# untitled.net
KiCad netlist of a schematic drawn in EAGLE
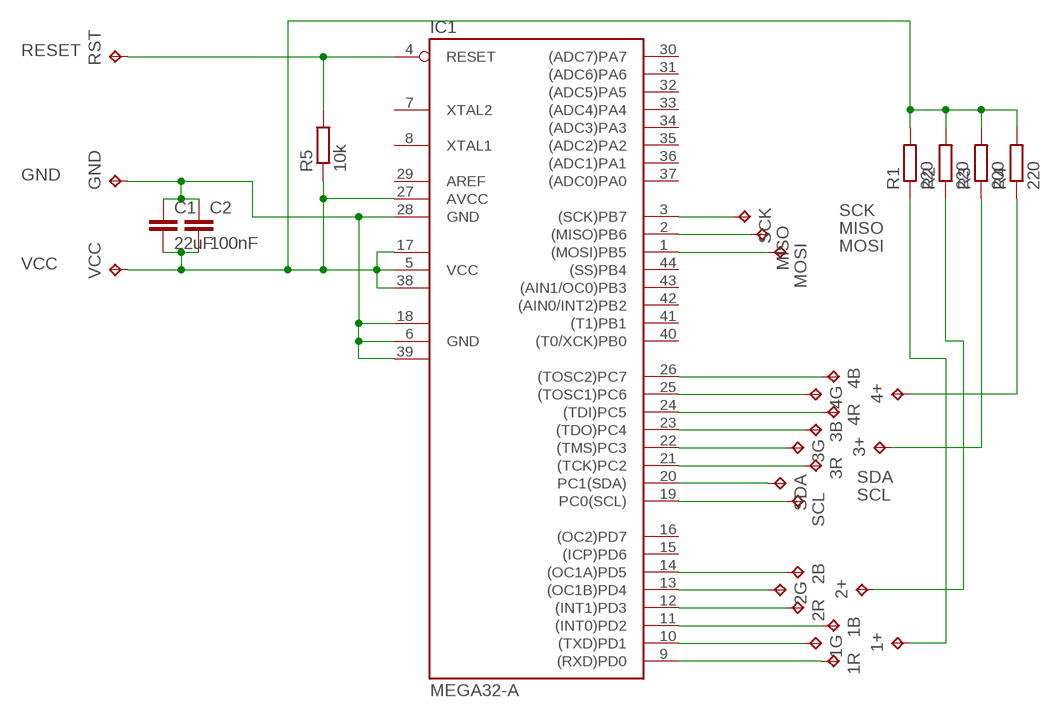
[diagram p0: schematic, sheet 1]

(export (version "E")
  (design (tool "Eeschema 10.0.6"))
  (components
    (comp (ref "1+")
      (value "TPTP19SQ")
      (footprint "eagle-import:TP19SQ")
      (libsource (lib "eagle-import") (part "TPTP19SQ"))
    )
    (comp (ref "1B")
      (value "TPTP19SQ")
      (footprint "eagle-import:TP19SQ")
      (libsource (lib "eagle-import") (part "TPTP19SQ"))
    )
    (comp (ref "1G")
      (value "TPTP19SQ")
      (footprint "eagle-import:TP19SQ")
      (libsource (lib "eagle-import") (part "TPTP19SQ"))
    )
    (comp (ref "1R")
      (value "TPTP19SQ")
      (footprint "eagle-import:TP19SQ")
      (libsource (lib "eagle-import") (part "TPTP19SQ"))
    )
    (comp (ref "2+")
      (value "TPTP19SQ")
      (footprint "eagle-import:TP19SQ")
      (libsource (lib "eagle-import") (part "TPTP19SQ"))
    )
    (comp (ref "2B")
      (value "TPTP19SQ")
      (footprint "eagle-import:TP19SQ")
      (libsource (lib "eagle-import") (part "TPTP19SQ"))
    )
    (comp (ref "2G")
      (value "TPTP19SQ")
      (footprint "eagle-import:TP19SQ")
      (libsource (lib "eagle-import") (part "TPTP19SQ"))
    )
    (comp (ref "2R")
      (value "TPTP19SQ")
      (footprint "eagle-import:TP19SQ")
      (libsource (lib "eagle-import") (part "TPTP19SQ"))
    )
    (comp (ref "3+")
      (value "TPTP19SQ")
      (footprint "eagle-import:TP19SQ")
      (libsource (lib "eagle-import") (part "TPTP19SQ"))
    )
    (comp (ref "3B")
      (value "TPTP19SQ")
      (footprint "eagle-import:TP19SQ")
      (libsource (lib "eagle-import") (part "TPTP19SQ"))
    )
    (comp (ref "3G")
      (value "TPTP19SQ")
      (footprint "eagle-import:TP19SQ")
      (libsource (lib "eagle-import") (part "TPTP19SQ"))
    )
    (comp (ref "3R")
      (value "TPTP19SQ")
      (footprint "eagle-import:TP19SQ")
      (libsource (lib "eagle-import") (part "TPTP19SQ"))
    )
    (comp (ref "4+")
      (value "TPTP19SQ")
      (footprint "eagle-import:TP19SQ")
      (libsource (lib "eagle-import") (part "TPTP19SQ"))
    )
    (comp (ref "4B")
      (value "TPTP19SQ")
      (footprint "eagle-import:TP19SQ")
      (libsource (lib "eagle-import") (part "TPTP19SQ"))
    )
    (comp (ref "4G")
      (value "TPTP19SQ")
      (footprint "eagle-import:TP19SQ")
      (libsource (lib "eagle-import") (part "TPTP19SQ"))
    )
    (comp (ref "4R")
      (value "TPTP19SQ")
      (footprint "eagle-import:TP19SQ")
      (libsource (lib "eagle-import") (part "TPTP19SQ"))
    )
    (comp (ref "C1")
      (value "22uF")
      (footprint "eagle-import:C025-024X044")
      (libsource (lib "eagle-import") (part "C-EU025-024X044"))
    )
    (comp (ref "C2")
      (value "100nF")
      (footprint "eagle-import:C025-024X044")
      (libsource (lib "eagle-import") (part "C-EU025-024X044"))
    )
    (comp (ref "GND")
      (value "TPTP19SQ")
      (footprint "eagle-import:TP19SQ")
      (libsource (lib "eagle-import") (part "TPTP19SQ"))
    )
    (comp (ref "IC1")
      (value "MEGA32-A")
      (footprint "eagle-import:TQFP44")
      (fields (field (name "MPN") "ATMEGA32-16AU"))
      (libsource (lib "eagle-import") (part "MEGA32-A"))
    )
    (comp (ref "MISO")
      (value "TPTP19SQ")
      (footprint "eagle-import:TP19SQ")
      (libsource (lib "eagle-import") (part "TPTP19SQ"))
    )
    (comp (ref "MOSI")
      (value "TPTP19SQ")
      (footprint "eagle-import:TP19SQ")
      (libsource (lib "eagle-import") (part "TPTP19SQ"))
    )
    (comp (ref "R1")
      (value "220")
      (footprint "eagle-import:M0805")
      (libsource (lib "eagle-import") (part "R-EU_M0805"))
    )
    (comp (ref "R2")
      (value "220")
      (footprint "eagle-import:M0805")
      (libsource (lib "eagle-import") (part "R-EU_M0805"))
    )
    (comp (ref "R3")
      (value "200")
      (footprint "eagle-import:M0805")
      (libsource (lib "eagle-import") (part "R-EU_M0805"))
    )
    (comp (ref "R4")
      (value "220")
      (footprint "eagle-import:M0805")
      (libsource (lib "eagle-import") (part "R-EU_M0805"))
    )
    (comp (ref "R5")
      (value "10k")
      (footprint "eagle-import:M0805")
      (libsource (lib "eagle-import") (part "R-EU_M0805"))
    )
    (comp (ref "RST")
      (value "TPTP19SQ")
      (footprint "eagle-import:TP19SQ")
      (libsource (lib "eagle-import") (part "TPTP19SQ"))
    )
    (comp (ref "SCK")
      (value "SCK")
      (footprint "eagle-import:TP19SQ")
      (libsource (lib "eagle-import") (part "TPTP19SQ"))
    )
    (comp (ref "SCL")
      (value "TPTP19SQ")
      (footprint "eagle-import:TP19SQ")
      (libsource (lib "eagle-import") (part "TPTP19SQ"))
    )
    (comp (ref "SDA")
      (value "TPTP19SQ")
      (footprint "eagle-import:TP19SQ")
      (libsource (lib "eagle-import") (part "TPTP19SQ"))
    )
    (comp (ref "VCC")
      (value "TPTP19SQ")
      (footprint "eagle-import:TP19SQ")
      (libsource (lib "eagle-import") (part "TPTP19SQ"))
    )
  )
  (nets
    (net (code "1") (name "/GND") (class "Default")
      (node (ref "C1") (pin "1") (pinfunction "1_1") (pintype "passive"))
      (node (ref "C2") (pin "1") (pinfunction "1_1") (pintype "passive"))
      (node (ref "GND") (pin "TP") (pinfunction "TP_TP") (pintype "input"))
      (node (ref "IC1") (pin "18") (pinfunction "GND1_18") (pintype "power_in"))
      (node (ref "IC1") (pin "28") (pinfunction "GND_28") (pintype "power_in"))
      (node (ref "IC1") (pin "39") (pinfunction "GND2_39") (pintype "power_in"))
      (node (ref "IC1") (pin "6") (pinfunction "GND_6") (pintype "power_in"))
    )
    (net (code "2") (name "/MISO") (class "Default")
      (node (ref "IC1") (pin "2") (pinfunction "(MISO)PB6_2") (pintype "bidirectional"))
      (node (ref "MISO") (pin "TP") (pinfunction "TP_TP") (pintype "input"))
    )
    (net (code "3") (name "/MOSI") (class "Default")
      (node (ref "IC1") (pin "1") (pinfunction "(MOSI)PB5_1") (pintype "bidirectional"))
      (node (ref "MOSI") (pin "TP") (pinfunction "TP_TP") (pintype "input"))
    )
    (net (code "4") (name "/RESET") (class "Default")
      (node (ref "IC1") (pin "4") (pinfunction "RESET_4") (pintype "input"))
      (node (ref "R5") (pin "2") (pinfunction "2_2") (pintype "passive"))
      (node (ref "RST") (pin "TP") (pinfunction "TP_TP") (pintype "input"))
    )
    (net (code "5") (name "/SCK") (class "Default")
      (node (ref "IC1") (pin "3") (pinfunction "(SCK)PB7_3") (pintype "bidirectional"))
      (node (ref "SCK") (pin "TP") (pinfunction "TP_TP") (pintype "input"))
    )
    (net (code "6") (name "/SCL") (class "Default")
      (node (ref "IC1") (pin "19") (pinfunction "PC0(SCL)_19") (pintype "bidirectional"))
      (node (ref "SCL") (pin "TP") (pinfunction "TP_TP") (pintype "input"))
    )
    (net (code "7") (name "/SDA") (class "Default")
      (node (ref "IC1") (pin "20") (pinfunction "PC1(SDA)_20") (pintype "bidirectional"))
      (node (ref "SDA") (pin "TP") (pinfunction "TP_TP") (pintype "input"))
    )
    (net (code "8") (name "/VCC") (class "Default")
      (node (ref "C1") (pin "2") (pinfunction "2_2") (pintype "passive"))
      (node (ref "C2") (pin "2") (pinfunction "2_2") (pintype "passive"))
      (node (ref "IC1") (pin "17") (pinfunction "VCC1_17") (pintype "power_in"))
      (node (ref "IC1") (pin "27") (pinfunction "AVCC_27") (pintype "power_in"))
      (node (ref "IC1") (pin "38") (pinfunction "VCC2_38") (pintype "power_in"))
      (node (ref "IC1") (pin "5") (pinfunction "VCC_5") (pintype "power_in"))
      (node (ref "R1") (pin "2") (pinfunction "2_2") (pintype "passive"))
      (node (ref "R2") (pin "2") (pinfunction "2_2") (pintype "passive"))
      (node (ref "R3") (pin "2") (pinfunction "2_2") (pintype "passive"))
      (node (ref "R4") (pin "2") (pinfunction "2_2") (pintype "passive"))
      (node (ref "R5") (pin "1") (pinfunction "1_1") (pintype "passive"))
      (node (ref "VCC") (pin "TP") (pinfunction "TP_TP") (pintype "input"))
    )
    (net (code "9") (name "Net-(1+-PadTP)") (class "Default")
      (node (ref "1+") (pin "TP") (pinfunction "TP_TP") (pintype "input"))
      (node (ref "R1") (pin "1") (pinfunction "1_1") (pintype "passive"))
    )
    (net (code "10") (name "Net-(2+-PadTP)") (class "Default")
      (node (ref "2+") (pin "TP") (pinfunction "TP_TP") (pintype "input"))
      (node (ref "R2") (pin "1") (pinfunction "1_1") (pintype "passive"))
    )
    (net (code "11") (name "Net-(3+-PadTP)") (class "Default")
      (node (ref "3+") (pin "TP") (pinfunction "TP_TP") (pintype "input"))
      (node (ref "R3") (pin "1") (pinfunction "1_1") (pintype "passive"))
    )
    (net (code "12") (name "Net-(4+-PadTP)") (class "Default")
      (node (ref "4+") (pin "TP") (pinfunction "TP_TP") (pintype "input"))
      (node (ref "R4") (pin "1") (pinfunction "1_1") (pintype "passive"))
    )
    (net (code "13") (name "Net-(IC1-(INT0)PD2)") (class "Default")
      (node (ref "1B") (pin "TP") (pinfunction "TP_TP") (pintype "input"))
      (node (ref "IC1") (pin "11") (pinfunction "(INT0)PD2_11") (pintype "bidirectional"))
    )
    (net (code "14") (name "Net-(IC1-(INT1)PD3)") (class "Default")
      (node (ref "2R") (pin "TP") (pinfunction "TP_TP") (pintype "input"))
      (node (ref "IC1") (pin "12") (pinfunction "(INT1)PD3_12") (pintype "bidirectional"))
    )
    (net (code "15") (name "Net-(IC1-(OC1A)PD5)") (class "Default")
      (node (ref "2B") (pin "TP") (pinfunction "TP_TP") (pintype "input"))
      (node (ref "IC1") (pin "14") (pinfunction "(OC1A)PD5_14") (pintype "bidirectional"))
    )
    (net (code "16") (name "Net-(IC1-(OC1B)PD4)") (class "Default")
      (node (ref "2G") (pin "TP") (pinfunction "TP_TP") (pintype "input"))
      (node (ref "IC1") (pin "13") (pinfunction "(OC1B)PD4_13") (pintype "bidirectional"))
    )
    (net (code "17") (name "Net-(IC1-(RXD)PD0)") (class "Default")
      (node (ref "1R") (pin "TP") (pinfunction "TP_TP") (pintype "input"))
      (node (ref "IC1") (pin "9") (pinfunction "(RXD)PD0_9") (pintype "bidirectional"))
    )
    (net (code "18") (name "Net-(IC1-(TCK)PC2)") (class "Default")
      (node (ref "3R") (pin "TP") (pinfunction "TP_TP") (pintype "input"))
      (node (ref "IC1") (pin "21") (pinfunction "(TCK)PC2_21") (pintype "bidirectional"))
    )
    (net (code "19") (name "Net-(IC1-(TDI)PC5)") (class "Default")
      (node (ref "4R") (pin "TP") (pinfunction "TP_TP") (pintype "input"))
      (node (ref "IC1") (pin "24") (pinfunction "(TDI)PC5_24") (pintype "bidirectional"))
    )
    (net (code "20") (name "Net-(IC1-(TDO)PC4)") (class "Default")
      (node (ref "3B") (pin "TP") (pinfunction "TP_TP") (pintype "input"))
      (node (ref "IC1") (pin "23") (pinfunction "(TDO)PC4_23") (pintype "bidirectional"))
    )
    (net (code "21") (name "Net-(IC1-(TMS)PC3)") (class "Default")
      (node (ref "3G") (pin "TP") (pinfunction "TP_TP") (pintype "input"))
      (node (ref "IC1") (pin "22") (pinfunction "(TMS)PC3_22") (pintype "bidirectional"))
    )
    (net (code "22") (name "Net-(IC1-(TOSC1)PC6)") (class "Default")
      (node (ref "4G") (pin "TP") (pinfunction "TP_TP") (pintype "input"))
      (node (ref "IC1") (pin "25") (pinfunction "(TOSC1)PC6_25") (pintype "bidirectional"))
    )
    (net (code "23") (name "Net-(IC1-(TOSC2)PC7)") (class "Default")
      (node (ref "4B") (pin "TP") (pinfunction "TP_TP") (pintype "input"))
      (node (ref "IC1") (pin "26") (pinfunction "(TOSC2)PC7_26") (pintype "bidirectional"))
    )
    (net (code "24") (name "Net-(IC1-(TXD)PD1)") (class "Default")
      (node (ref "1G") (pin "TP") (pinfunction "TP_TP") (pintype "input"))
      (node (ref "IC1") (pin "10") (pinfunction "(TXD)PD1_10") (pintype "bidirectional"))
    )
    (net (code "25") (name "unconnected-(IC1-(ADC0)PA0-Pad37)") (class "Default")
      (node (ref "IC1") (pin "37") (pinfunction "(ADC0)PA0_37") (pintype "bidirectional"))
    )
    (net (code "26") (name "unconnected-(IC1-(ADC1)PA1-Pad36)") (class "Default")
      (node (ref "IC1") (pin "36") (pinfunction "(ADC1)PA1_36") (pintype "bidirectional"))
    )
    (net (code "27") (name "unconnected-(IC1-(ADC2)PA2-Pad35)") (class "Default")
      (node (ref "IC1") (pin "35") (pinfunction "(ADC2)PA2_35") (pintype "bidirectional"))
    )
    (net (code "28") (name "unconnected-(IC1-(ADC3)PA3-Pad34)") (class "Default")
      (node (ref "IC1") (pin "34") (pinfunction "(ADC3)PA3_34") (pintype "bidirectional"))
    )
    (net (code "29") (name "unconnected-(IC1-(ADC4)PA4-Pad33)") (class "Default")
      (node (ref "IC1") (pin "33") (pinfunction "(ADC4)PA4_33") (pintype "bidirectional"))
    )
    (net (code "30") (name "unconnected-(IC1-(ADC5)PA5-Pad32)") (class "Default")
      (node (ref "IC1") (pin "32") (pinfunction "(ADC5)PA5_32") (pintype "bidirectional"))
    )
    (net (code "31") (name "unconnected-(IC1-(ADC6)PA6-Pad31)") (class "Default")
      (node (ref "IC1") (pin "31") (pinfunction "(ADC6)PA6_31") (pintype "bidirectional"))
    )
    (net (code "32") (name "unconnected-(IC1-(ADC7)PA7-Pad30)") (class "Default")
      (node (ref "IC1") (pin "30") (pinfunction "(ADC7)PA7_30") (pintype "bidirectional"))
    )
    (net (code "33") (name "unconnected-(IC1-(AIN0{slash}INT2)PB2-Pad42)") (class "Default")
      (node (ref "IC1") (pin "42") (pinfunction "(AIN0/INT2)PB2_42") (pintype "bidirectional"))
    )
    (net (code "34") (name "unconnected-(IC1-(AIN1{slash}OC0)PB3-Pad43)") (class "Default")
      (node (ref "IC1") (pin "43") (pinfunction "(AIN1/OC0)PB3_43") (pintype "bidirectional"))
    )
    (net (code "35") (name "unconnected-(IC1-(ICP)PD6-Pad15)") (class "Default")
      (node (ref "IC1") (pin "15") (pinfunction "(ICP)PD6_15") (pintype "bidirectional"))
    )
    (net (code "36") (name "unconnected-(IC1-(OC2)PD7-Pad16)") (class "Default")
      (node (ref "IC1") (pin "16") (pinfunction "(OC2)PD7_16") (pintype "bidirectional"))
    )
    (net (code "37") (name "unconnected-(IC1-(SS)PB4-Pad44)") (class "Default")
      (node (ref "IC1") (pin "44") (pinfunction "(SS)PB4_44") (pintype "bidirectional"))
    )
    (net (code "38") (name "unconnected-(IC1-(T0{slash}XCK)PB0-Pad40)") (class "Default")
      (node (ref "IC1") (pin "40") (pinfunction "(T0/XCK)PB0_40") (pintype "bidirectional"))
    )
    (net (code "39") (name "unconnected-(IC1-(T1)PB1-Pad41)") (class "Default")
      (node (ref "IC1") (pin "41") (pinfunction "(T1)PB1_41") (pintype "bidirectional"))
    )
    (net (code "40") (name "unconnected-(IC1-AREF-Pad29)") (class "Default")
      (node (ref "IC1") (pin "29") (pinfunction "AREF_29") (pintype "passive"))
    )
    (net (code "41") (name "unconnected-(IC1-XTAL1-Pad8)") (class "Default")
      (node (ref "IC1") (pin "8") (pinfunction "XTAL1_8") (pintype "bidirectional"))
    )
    (net (code "42") (name "unconnected-(IC1-XTAL2-Pad7)") (class "Default")
      (node (ref "IC1") (pin "7") (pinfunction "XTAL2_7") (pintype "bidirectional"))
    )
  )
)
